# Power_3.net
KiCad netlist of a schematic drawn in Altium Designer
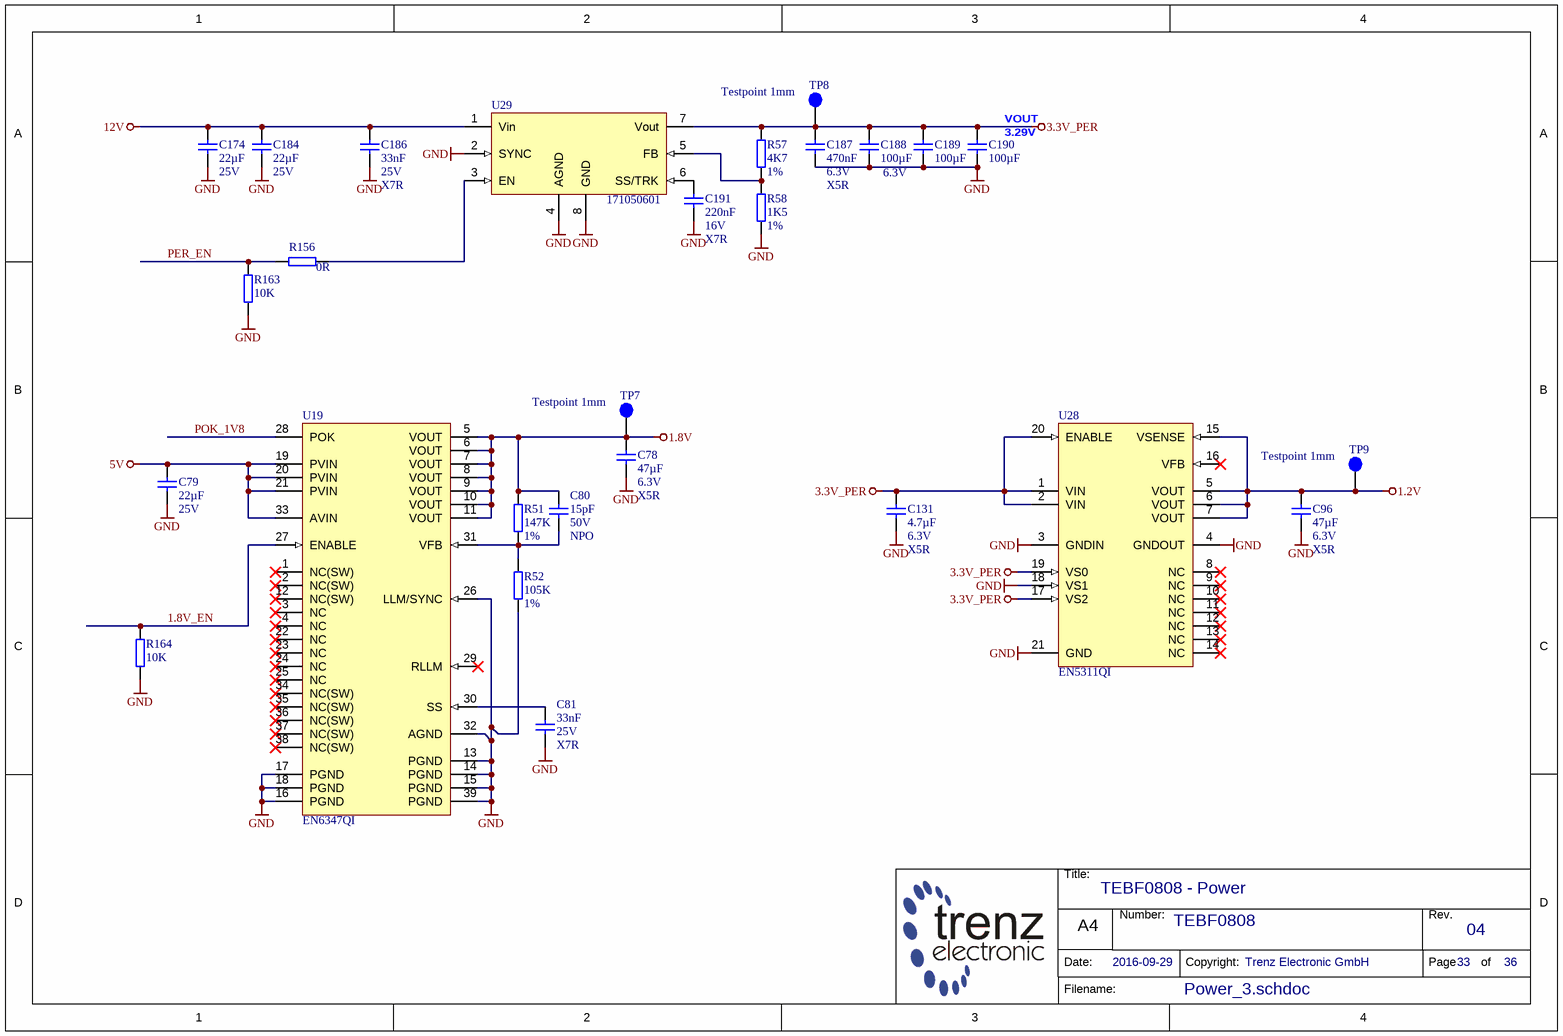
[diagram p0: Power_3.schdoc]

(export (version "E")
  (design (tool "Eeschema 10.0.6"))
  (components
    (comp (ref "C78")
      (value "47µF")
      (footprint "CAPC3216X180N")
      (description "KON 47µF 6.3V  X5R SMD 20%")
      (fields
        (field (name "VOLTAGE") "6.3V")
        (field (name "TECHNOLOGY") "X5R")
        (field (name "TOLERANCE") "20%")
      )
      (libsource (lib "TE") (part "CAP-NP"))
    )
    (comp (ref "C79")
      (value "22µF")
      (footprint "CAPC3216X180N")
      (description "KON 22µF X5R 25V SMD 10%")
      (fields (field (name "VOLTAGE") "25V") (field (name "TOLERANCE") "10%"))
      (libsource (lib "TE") (part "CAP-NP"))
    )
    (comp (ref "C80")
      (value "15pF")
      (footprint "CAPC1005X55N")
      (description "KON 15pF NPO 50V SMD")
      (fields (field (name "VOLTAGE") "50V") (field (name "TECHNOLOGY") "NPO"))
      (libsource (lib "TE") (part "CAP-NP"))
    )
    (comp (ref "C81")
      (value "33nF")
      (footprint "CAPC1005X55N")
      (description "KON 33nF 25V X7R SMD")
      (fields (field (name "VOLTAGE") "25V") (field (name "TECHNOLOGY") "X7R"))
      (libsource (lib "TE") (part "CAP-NP"))
    )
    (comp (ref "C96")
      (value "47µF")
      (footprint "CAPC3216X180N")
      (description "KON 47µF 6.3V  X5R SMD 20%")
      (fields
        (field (name "VOLTAGE") "6.3V")
        (field (name "TECHNOLOGY") "X5R")
        (field (name "TOLERANCE") "20%")
      )
      (libsource (lib "TE") (part "CAP-NP"))
    )
    (comp (ref "C131")
      (value "4.7µF")
      (footprint "CAPC1005X60N")
      (description "KON 4.7µF 6.3V X5R SMD 20%")
      (fields
        (field (name "VOLTAGE") "6.3V")
        (field (name "TECHNOLOGY") "X5R")
        (field (name "TOLERANCE") "20%")
      )
      (libsource (lib "TE") (part "CAP-NP"))
    )
    (comp (ref "C174")
      (value "22µF")
      (footprint "CAPC3216X180N")
      (description "KON 22µF X5R 25V SMD 10%")
      (fields (field (name "VOLTAGE") "25V") (field (name "TOLERANCE") "10%"))
      (libsource (lib "TE") (part "CAP-NP"))
    )
    (comp (ref "C184")
      (value "22µF")
      (footprint "CAPC3216X180N")
      (description "KON 22µF X5R 25V SMD 10%")
      (fields (field (name "VOLTAGE") "25V") (field (name "TOLERANCE") "10%"))
      (libsource (lib "TE") (part "CAP-NP"))
    )
    (comp (ref "C186")
      (value "33nF")
      (footprint "CAPC1005X55N")
      (description "KON 33nF 25V X7R SMD")
      (fields (field (name "VOLTAGE") "25V") (field (name "TECHNOLOGY") "X7R"))
      (libsource (lib "TE") (part "CAP-NP"))
    )
    (comp (ref "C187")
      (value "470nF")
      (footprint "CAPC1005X55N")
      (description "KON 470nF 6,3V X5R SMD")
      (fields (field (name "VOLTAGE") "6.3V") (field (name "TECHNOLOGY") "X5R"))
      (libsource (lib "TE") (part "CAP-NP"))
    )
    (comp (ref "C188")
      (value "100µF")
      (footprint "CAPC3216X180N")
      (description "KON 100µF 6,3V X5R SMD 20%")
      (fields (field (name "TOLERANCE") "20%") (field (name "VOLTAGE") "6.3V"))
      (libsource (lib "TE") (part "CAP-NP"))
    )
    (comp (ref "C189")
      (value "100µF")
      (footprint "CAPC3216X180N")
      (description "KON 100µF 6,3V X5R SMD 20%")
      (fields (field (name "TOLERANCE") "20%") (field (name "VOLTAGE") "6.3V"))
      (libsource (lib "TE") (part "CAP-NP"))
    )
    (comp (ref "C190")
      (value "100µF")
      (footprint "CAPC3216X180N")
      (description "KON 100µF 6,3V X5R SMD 20%")
      (fields (field (name "TOLERANCE") "20%") (field (name "VOLTAGE") "6.3V"))
      (libsource (lib "TE") (part "CAP-NP"))
    )
    (comp (ref "C191")
      (value "220nF")
      (footprint "CAPC1005X55N")
      (description "KON 220nF 16V X7R SMD")
      (fields (field (name "VOLTAGE") "16V") (field (name "TECHNOLOGY") "X7R"))
      (libsource (lib "TE") (part "CAP-NP"))
    )
    (comp (ref "R51")
      (value "147K")
      (footprint "RESC1005X40N")
      (description "WID SMD 147K 1% 0,063W")
      (fields (field (name "TOLERANCE") "1%"))
      (libsource (lib "TE") (part "RES"))
    )
    (comp (ref "R52")
      (value "105K")
      (footprint "RESC1005X40N")
      (description "WID SMD 105K 1% 0,063W")
      (fields (field (name "TOLERANCE") "1%"))
      (libsource (lib "TE") (part "RES"))
    )
    (comp (ref "R57")
      (value "4K7")
      (footprint "RESC1005X40N")
      (description "WID SMD 4K7 1% 0,063W")
      (fields (field (name "TOLERANCE") "1%"))
      (libsource (lib "TE") (part "RES"))
    )
    (comp (ref "R58")
      (value "1K5")
      (footprint "RESC1005X40N")
      (description "WID SMD 1K5 1% 0,063W")
      (fields (field (name "TOLERANCE") "1%"))
      (libsource (lib "TE") (part "RES"))
    )
    (comp (ref "R156")
      (value "0R")
      (footprint "RESC1005X40N")
      (description "WID SMD 0R")
      (fields (field (name "TOLERANCE") "1%"))
      (libsource (lib "TE") (part "RES"))
    )
    (comp (ref "R163")
      (value "10K")
      (footprint "RESC1005X40N")
      (description "WID SMD 10K 1% 0,063W")
      (fields (field (name "TOLERANCE") "1%"))
      (libsource (lib "TE") (part "RES"))
    )
    (comp (ref "R164")
      (value "10K")
      (footprint "RESC1005X40N")
      (description "WID SMD 10K 1% 0,063W")
      (fields (field (name "TOLERANCE") "1%"))
      (libsource (lib "TE") (part "RES"))
    )
    (comp (ref "TP7") (value "Testpoint 1mm") (footprint "TP_1mm") (libsource (lib "TE") (part "TP")))
    (comp (ref "TP8") (value "Testpoint 1mm") (footprint "TP_1mm") (libsource (lib "TE") (part "TP")))
    (comp (ref "TP9") (value "Testpoint 1mm") (footprint "TP_1mm") (libsource (lib "TE") (part "TP")))
    (comp (ref "U19") (value "EN6347QI") (footprint "EN63xx") (libsource (lib "TE") (part "EN63xx")))
    (comp (ref "U28") (value "EN5311QI") (footprint "EN5311QI") (libsource (lib "TE") (part "EN5311QI")))
    (comp (ref "U29")
      (value "171050601")
      (footprint "7TO-PMOD")
      (libsource (lib "TE") (part "WE-DCDC-171050601"))
    )
  )
  (nets
    (net (code "1") (name "/1.8V_EN") (class "Default")
      (node (ref "R164") (pin "2") (pinfunction "2_2") (pintype "passive"))
      (node (ref "U19") (pin "27") (pinfunction "ENABLE_27") (pintype "input"))
    )
    (net (code "2") (name "/PER_EN") (class "Default")
      (node (ref "R156") (pin "2") (pinfunction "2_2") (pintype "passive"))
      (node (ref "R163") (pin "2") (pinfunction "2_2") (pintype "passive"))
    )
    (net (code "3") (name "/POK_1V8") (class "Default")
      (node (ref "U19") (pin "28") (pinfunction "POK_28") (pintype "open_collector"))
    )
    (net (code "4") (name "1.2V") (class "Default")
      (node (ref "C96") (pin "1") (pinfunction "1_1") (pintype "passive"))
      (node (ref "TP9") (pin "1") (pintype "passive"))
      (node (ref "U28") (pin "15") (pinfunction "VSENSE_15") (pintype "input"))
      (node (ref "U28") (pin "5") (pinfunction "VOUT_5") (pintype "power_in"))
      (node (ref "U28") (pin "6") (pinfunction "VOUT_6") (pintype "power_in"))
      (node (ref "U28") (pin "7") (pinfunction "VOUT_7") (pintype "power_in"))
    )
    (net (code "5") (name "1.8V") (class "Default")
      (node (ref "C78") (pin "1") (pinfunction "1_1") (pintype "passive"))
      (node (ref "C80") (pin "1") (pinfunction "1_1") (pintype "passive"))
      (node (ref "R51") (pin "2") (pinfunction "2_2") (pintype "passive"))
      (node (ref "TP7") (pin "1") (pintype "passive"))
      (node (ref "U19") (pin "10") (pinfunction "VOUT_10") (pintype "power_in"))
      (node (ref "U19") (pin "11") (pinfunction "VOUT_11") (pintype "power_in"))
      (node (ref "U19") (pin "5") (pinfunction "VOUT_5") (pintype "power_in"))
      (node (ref "U19") (pin "6") (pinfunction "VOUT_6") (pintype "power_in"))
      (node (ref "U19") (pin "7") (pinfunction "VOUT_7") (pintype "power_in"))
      (node (ref "U19") (pin "8") (pinfunction "VOUT_8") (pintype "power_in"))
      (node (ref "U19") (pin "9") (pinfunction "VOUT_9") (pintype "power_in"))
    )
    (net (code "6") (name "3.3V_PER") (class "Default")
      (node (ref "C131") (pin "1") (pinfunction "1_1") (pintype "passive"))
      (node (ref "C187") (pin "1") (pinfunction "1_1") (pintype "passive"))
      (node (ref "C188") (pin "1") (pinfunction "1_1") (pintype "passive"))
      (node (ref "C189") (pin "1") (pinfunction "1_1") (pintype "passive"))
      (node (ref "C190") (pin "1") (pinfunction "1_1") (pintype "passive"))
      (node (ref "R57") (pin "1") (pinfunction "1_1") (pintype "passive"))
      (node (ref "TP8") (pin "1") (pintype "passive"))
      (node (ref "U28") (pin "1") (pinfunction "VIN_1") (pintype "power_in"))
      (node (ref "U28") (pin "17") (pinfunction "VS2_17") (pintype "input"))
      (node (ref "U28") (pin "19") (pinfunction "VS0_19") (pintype "input"))
      (node (ref "U28") (pin "2") (pinfunction "VIN_2") (pintype "power_in"))
      (node (ref "U28") (pin "20") (pinfunction "ENABLE_20") (pintype "input"))
      (node (ref "U29") (pin "7") (pinfunction "Vout_7") (pintype "power_in"))
    )
    (net (code "7") (name "5V") (class "Default")
      (node (ref "C79") (pin "2") (pinfunction "2_2") (pintype "passive"))
      (node (ref "U19") (pin "19") (pinfunction "PVIN_19") (pintype "power_in"))
      (node (ref "U19") (pin "20") (pinfunction "PVIN_20") (pintype "power_in"))
      (node (ref "U19") (pin "21") (pinfunction "PVIN_21") (pintype "power_in"))
      (node (ref "U19") (pin "33") (pinfunction "AVIN_33") (pintype "power_in"))
    )
    (net (code "8") (name "12V") (class "Default")
      (node (ref "C174") (pin "2") (pinfunction "2_2") (pintype "passive"))
      (node (ref "C184") (pin "2") (pinfunction "2_2") (pintype "passive"))
      (node (ref "C186") (pin "1") (pinfunction "1_1") (pintype "passive"))
      (node (ref "U29") (pin "1") (pinfunction "Vin_1") (pintype "power_in"))
    )
    (net (code "9") (name "GND") (class "Default")
      (node (ref "C131") (pin "2") (pinfunction "2_2") (pintype "passive"))
      (node (ref "C174") (pin "1") (pinfunction "1_1") (pintype "passive"))
      (node (ref "C184") (pin "1") (pinfunction "1_1") (pintype "passive"))
      (node (ref "C186") (pin "2") (pinfunction "2_2") (pintype "passive"))
      (node (ref "C187") (pin "2") (pinfunction "2_2") (pintype "passive"))
      (node (ref "C188") (pin "2") (pinfunction "2_2") (pintype "passive"))
      (node (ref "C189") (pin "2") (pinfunction "2_2") (pintype "passive"))
      (node (ref "C190") (pin "2") (pinfunction "2_2") (pintype "passive"))
      (node (ref "C191") (pin "2") (pinfunction "2_2") (pintype "passive"))
      (node (ref "C78") (pin "2") (pinfunction "2_2") (pintype "passive"))
      (node (ref "C79") (pin "1") (pinfunction "1_1") (pintype "passive"))
      (node (ref "C81") (pin "2") (pinfunction "2_2") (pintype "passive"))
      (node (ref "C96") (pin "2") (pinfunction "2_2") (pintype "passive"))
      (node (ref "R163") (pin "1") (pinfunction "1_1") (pintype "passive"))
      (node (ref "R164") (pin "1") (pinfunction "1_1") (pintype "passive"))
      (node (ref "R52") (pin "2") (pinfunction "2_2") (pintype "passive"))
      (node (ref "R58") (pin "2") (pinfunction "2_2") (pintype "passive"))
      (node (ref "U19") (pin "13") (pinfunction "PGND_13") (pintype "power_in"))
      (node (ref "U19") (pin "14") (pinfunction "PGND_14") (pintype "power_in"))
      (node (ref "U19") (pin "15") (pinfunction "PGND_15") (pintype "power_in"))
      (node (ref "U19") (pin "16") (pinfunction "PGND_16") (pintype "power_in"))
      (node (ref "U19") (pin "17") (pinfunction "PGND_17") (pintype "power_in"))
      (node (ref "U19") (pin "18") (pinfunction "PGND_18") (pintype "power_in"))
      (node (ref "U19") (pin "26") (pinfunction "LLM/SYNC_26") (pintype "input"))
      (node (ref "U19") (pin "32") (pinfunction "AGND_32") (pintype "power_in"))
      (node (ref "U19") (pin "39") (pinfunction "PGND_39") (pintype "power_in"))
      (node (ref "U28") (pin "18") (pinfunction "VS1_18") (pintype "input"))
      (node (ref "U28") (pin "21") (pinfunction "GND_21") (pintype "power_in"))
      (node (ref "U28") (pin "3") (pinfunction "GNDIN_3") (pintype "power_in"))
      (node (ref "U28") (pin "4") (pinfunction "GNDOUT_4") (pintype "power_in"))
      (node (ref "U29") (pin "2") (pinfunction "SYNC_2") (pintype "input"))
      (node (ref "U29") (pin "4") (pinfunction "AGND_4") (pintype "power_in"))
      (node (ref "U29") (pin "8") (pinfunction "GND_8") (pintype "power_in"))
    )
    (net (code "10") (name "Net-(U19-SS)") (class "Default")
      (node (ref "C81") (pin "1") (pinfunction "1_1") (pintype "passive"))
      (node (ref "U19") (pin "30") (pinfunction "SS_30") (pintype "input"))
    )
    (net (code "11") (name "Net-(U19-VFB)") (class "Default")
      (node (ref "C80") (pin "2") (pinfunction "2_2") (pintype "passive"))
      (node (ref "R51") (pin "1") (pinfunction "1_1") (pintype "passive"))
      (node (ref "R52") (pin "1") (pinfunction "1_1") (pintype "passive"))
      (node (ref "U19") (pin "31") (pinfunction "VFB_31") (pintype "input"))
    )
    (net (code "12") (name "Net-(U29-EN)") (class "Default")
      (node (ref "R156") (pin "1") (pinfunction "1_1") (pintype "passive"))
      (node (ref "U29") (pin "3") (pinfunction "EN_3") (pintype "input"))
    )
    (net (code "13") (name "Net-(U29-FB)") (class "Default")
      (node (ref "R57") (pin "2") (pinfunction "2_2") (pintype "passive"))
      (node (ref "R58") (pin "1") (pinfunction "1_1") (pintype "passive"))
      (node (ref "U29") (pin "5") (pinfunction "FB_5") (pintype "input"))
    )
    (net (code "14") (name "Net-(U29-SS{slash}TRK)") (class "Default")
      (node (ref "C191") (pin "1") (pinfunction "1_1") (pintype "passive"))
      (node (ref "U29") (pin "6") (pinfunction "SS/TRK_6") (pintype "input"))
    )
    (net (code "15") (name "unconnected-(U19-NC(SW)-Pad1)") (class "Default")
      (node (ref "U19") (pin "1") (pinfunction "NC(SW)_1") (pintype "passive+no_connect"))
    )
    (net (code "16") (name "unconnected-(U19-NC(SW)-Pad2)") (class "Default")
      (node (ref "U19") (pin "2") (pinfunction "NC(SW)_2") (pintype "passive+no_connect"))
    )
    (net (code "17") (name "unconnected-(U19-NC(SW)-Pad12)") (class "Default")
      (node (ref "U19") (pin "12") (pinfunction "NC(SW)_12") (pintype "passive+no_connect"))
    )
    (net (code "18") (name "unconnected-(U19-NC(SW)-Pad34)") (class "Default")
      (node (ref "U19") (pin "34") (pinfunction "NC(SW)_34") (pintype "passive+no_connect"))
    )
    (net (code "19") (name "unconnected-(U19-NC(SW)-Pad35)") (class "Default")
      (node (ref "U19") (pin "35") (pinfunction "NC(SW)_35") (pintype "passive+no_connect"))
    )
    (net (code "20") (name "unconnected-(U19-NC(SW)-Pad36)") (class "Default")
      (node (ref "U19") (pin "36") (pinfunction "NC(SW)_36") (pintype "passive+no_connect"))
    )
    (net (code "21") (name "unconnected-(U19-NC(SW)-Pad37)") (class "Default")
      (node (ref "U19") (pin "37") (pinfunction "NC(SW)_37") (pintype "passive+no_connect"))
    )
    (net (code "22") (name "unconnected-(U19-NC(SW)-Pad38)") (class "Default")
      (node (ref "U19") (pin "38") (pinfunction "NC(SW)_38") (pintype "passive+no_connect"))
    )
    (net (code "23") (name "unconnected-(U19-NC-Pad3)") (class "Default")
      (node (ref "U19") (pin "3") (pinfunction "NC_3") (pintype "passive+no_connect"))
    )
    (net (code "24") (name "unconnected-(U19-NC-Pad4)") (class "Default")
      (node (ref "U19") (pin "4") (pinfunction "NC_4") (pintype "passive+no_connect"))
    )
    (net (code "25") (name "unconnected-(U19-NC-Pad22)") (class "Default")
      (node (ref "U19") (pin "22") (pinfunction "NC_22") (pintype "passive+no_connect"))
    )
    (net (code "26") (name "unconnected-(U19-NC-Pad23)") (class "Default")
      (node (ref "U19") (pin "23") (pinfunction "NC_23") (pintype "passive+no_connect"))
    )
    (net (code "27") (name "unconnected-(U19-NC-Pad24)") (class "Default")
      (node (ref "U19") (pin "24") (pinfunction "NC_24") (pintype "passive+no_connect"))
    )
    (net (code "28") (name "unconnected-(U19-NC-Pad25)") (class "Default")
      (node (ref "U19") (pin "25") (pinfunction "NC_25") (pintype "passive+no_connect"))
    )
    (net (code "29") (name "unconnected-(U19-RLLM-Pad29)") (class "Default")
      (node (ref "U19") (pin "29") (pinfunction "RLLM_29") (pintype "input+no_connect"))
    )
    (net (code "30") (name "unconnected-(U28-NC-Pad8)") (class "Default")
      (node (ref "U28") (pin "8") (pinfunction "NC_8") (pintype "passive+no_connect"))
    )
    (net (code "31") (name "unconnected-(U28-NC-Pad9)") (class "Default")
      (node (ref "U28") (pin "9") (pinfunction "NC_9") (pintype "passive+no_connect"))
    )
    (net (code "32") (name "unconnected-(U28-NC-Pad10)") (class "Default")
      (node (ref "U28") (pin "10") (pinfunction "NC_10") (pintype "passive+no_connect"))
    )
    (net (code "33") (name "unconnected-(U28-NC-Pad11)") (class "Default")
      (node (ref "U28") (pin "11") (pinfunction "NC_11") (pintype "passive+no_connect"))
    )
    (net (code "34") (name "unconnected-(U28-NC-Pad12)") (class "Default")
      (node (ref "U28") (pin "12") (pinfunction "NC_12") (pintype "passive+no_connect"))
    )
    (net (code "35") (name "unconnected-(U28-NC-Pad13)") (class "Default")
      (node (ref "U28") (pin "13") (pinfunction "NC_13") (pintype "passive+no_connect"))
    )
    (net (code "36") (name "unconnected-(U28-NC-Pad14)") (class "Default")
      (node (ref "U28") (pin "14") (pinfunction "NC_14") (pintype "passive+no_connect"))
    )
    (net (code "37") (name "unconnected-(U28-VFB-Pad16)") (class "Default")
      (node (ref "U28") (pin "16") (pinfunction "VFB_16") (pintype "input+no_connect"))
    )
  )
)
